# parallelmonitor.net
KiCad netlist of a schematic drawn in EAGLE
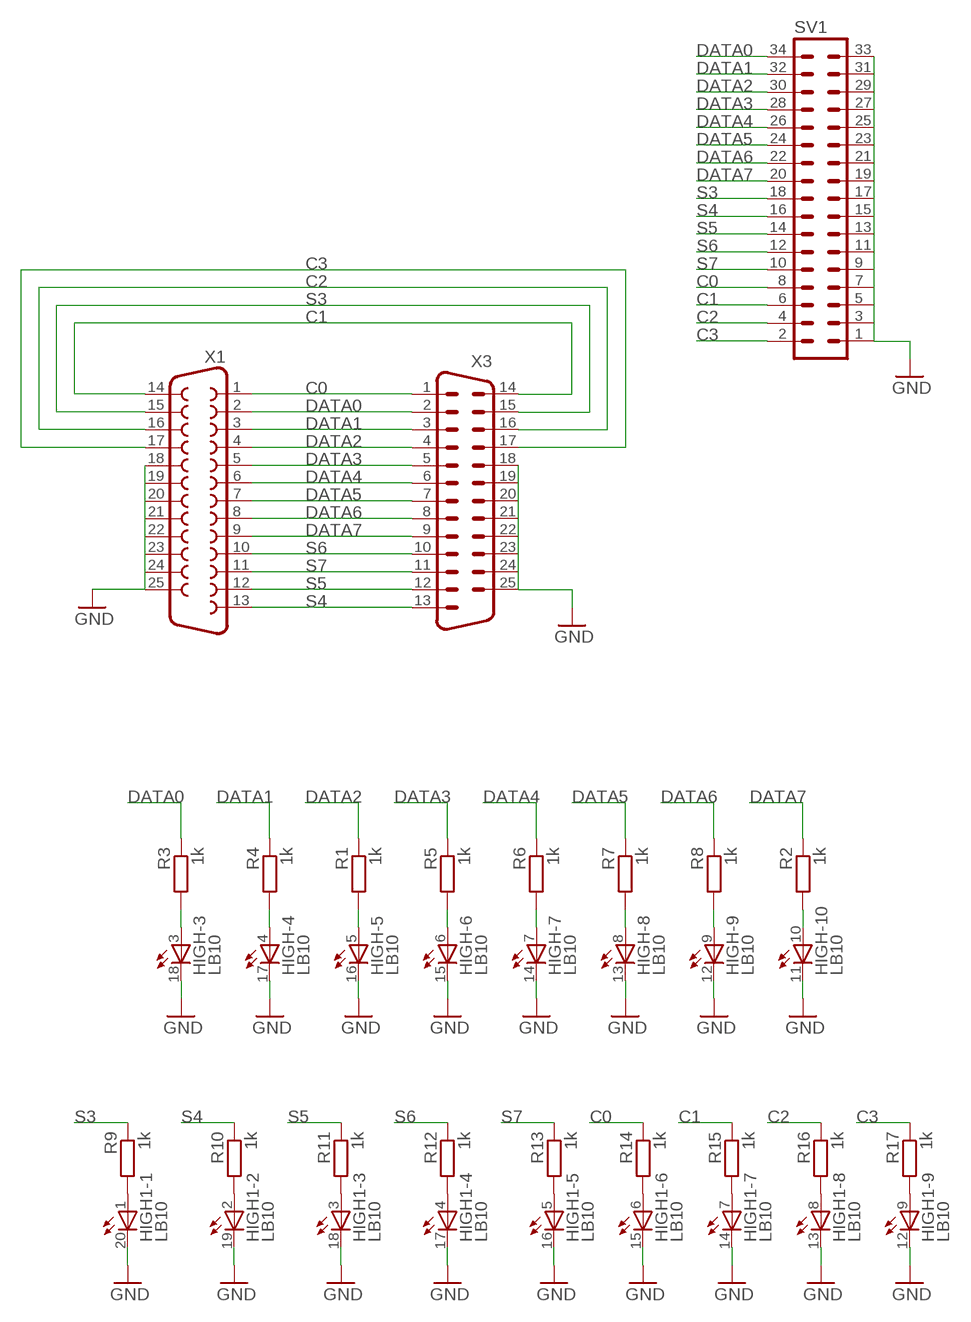
[diagram p0: schematic, sheet 1]

(export (version "E")
  (design (tool "Eeschema 10.0.6"))
  (components
    (comp (ref "HIGH")
      (value "LB10")
      (footprint "eagle-import:LB10")
      (libsource (lib "eagle-import") (part "LB10"))
    )
    (comp (ref "HIGH1")
      (value "LB10")
      (footprint "eagle-import:LB10")
      (libsource (lib "eagle-import") (part "LB10"))
    )
    (comp (ref "R1")
      (value "1k")
      (footprint "eagle-import:M0805")
      (libsource (lib "eagle-import") (part "R-EU_M0805"))
    )
    (comp (ref "R2")
      (value "1k")
      (footprint "eagle-import:M0805")
      (libsource (lib "eagle-import") (part "R-EU_M0805"))
    )
    (comp (ref "R3")
      (value "1k")
      (footprint "eagle-import:M0805")
      (libsource (lib "eagle-import") (part "R-EU_M0805"))
    )
    (comp (ref "R4")
      (value "1k")
      (footprint "eagle-import:M0805")
      (libsource (lib "eagle-import") (part "R-EU_M0805"))
    )
    (comp (ref "R5")
      (value "1k")
      (footprint "eagle-import:M0805")
      (libsource (lib "eagle-import") (part "R-EU_M0805"))
    )
    (comp (ref "R6")
      (value "1k")
      (footprint "eagle-import:M0805")
      (libsource (lib "eagle-import") (part "R-EU_M0805"))
    )
    (comp (ref "R7")
      (value "1k")
      (footprint "eagle-import:M0805")
      (libsource (lib "eagle-import") (part "R-EU_M0805"))
    )
    (comp (ref "R8")
      (value "1k")
      (footprint "eagle-import:M0805")
      (libsource (lib "eagle-import") (part "R-EU_M0805"))
    )
    (comp (ref "R9")
      (value "1k")
      (footprint "eagle-import:M0805")
      (libsource (lib "eagle-import") (part "R-EU_M0805"))
    )
    (comp (ref "R10")
      (value "1k")
      (footprint "eagle-import:M0805")
      (libsource (lib "eagle-import") (part "R-EU_M0805"))
    )
    (comp (ref "R11")
      (value "1k")
      (footprint "eagle-import:M0805")
      (libsource (lib "eagle-import") (part "R-EU_M0805"))
    )
    (comp (ref "R12")
      (value "1k")
      (footprint "eagle-import:M0805")
      (libsource (lib "eagle-import") (part "R-EU_M0805"))
    )
    (comp (ref "R13")
      (value "1k")
      (footprint "eagle-import:M0805")
      (libsource (lib "eagle-import") (part "R-EU_M0805"))
    )
    (comp (ref "R14")
      (value "1k")
      (footprint "eagle-import:M0805")
      (libsource (lib "eagle-import") (part "R-EU_M0805"))
    )
    (comp (ref "R15")
      (value "1k")
      (footprint "eagle-import:M0805")
      (libsource (lib "eagle-import") (part "R-EU_M0805"))
    )
    (comp (ref "R16")
      (value "1k")
      (footprint "eagle-import:M0805")
      (libsource (lib "eagle-import") (part "R-EU_M0805"))
    )
    (comp (ref "R17")
      (value "1k")
      (footprint "eagle-import:M0805")
      (libsource (lib "eagle-import") (part "R-EU_M0805"))
    )
    (comp (ref "SV1")
      (value "MA17-2W")
      (footprint "eagle-import:MA17-2W")
      (libsource (lib "eagle-import") (part "MA17-2W"))
    )
    (comp (ref "X1")
      (value "F25D")
      (footprint "eagle-import:F25D")
      (libsource (lib "eagle-import") (part "F25D"))
    )
    (comp (ref "X3")
      (value "M25D")
      (footprint "eagle-import:M25D")
      (libsource (lib "eagle-import") (part "M25D"))
    )
  )
  (nets
    (net (code "1") (name "/C0") (class "Default")
      (node (ref "R14") (pin "1") (pinfunction "1_1") (pintype "passive"))
      (node (ref "SV1") (pin "8") (pinfunction "8_8") (pintype "passive"))
      (node (ref "X1") (pin "1") (pinfunction "1_1") (pintype "passive"))
      (node (ref "X3") (pin "1") (pinfunction "1_1") (pintype "passive"))
    )
    (net (code "2") (name "/C1") (class "Default")
      (node (ref "R15") (pin "1") (pinfunction "1_1") (pintype "passive"))
      (node (ref "SV1") (pin "6") (pinfunction "6_6") (pintype "passive"))
      (node (ref "X1") (pin "14") (pinfunction "14_14") (pintype "passive"))
      (node (ref "X3") (pin "14") (pinfunction "14_14") (pintype "passive"))
    )
    (net (code "3") (name "/C2") (class "Default")
      (node (ref "R16") (pin "1") (pinfunction "1_1") (pintype "passive"))
      (node (ref "SV1") (pin "4") (pinfunction "4_4") (pintype "passive"))
      (node (ref "X1") (pin "16") (pinfunction "16_16") (pintype "passive"))
      (node (ref "X3") (pin "16") (pinfunction "16_16") (pintype "passive"))
    )
    (net (code "4") (name "/C3") (class "Default")
      (node (ref "R17") (pin "1") (pinfunction "1_1") (pintype "passive"))
      (node (ref "SV1") (pin "2") (pinfunction "2_2") (pintype "passive"))
      (node (ref "X1") (pin "17") (pinfunction "17_17") (pintype "passive"))
      (node (ref "X3") (pin "17") (pinfunction "17_17") (pintype "passive"))
    )
    (net (code "5") (name "/DATA0") (class "Default")
      (node (ref "R3") (pin "1") (pinfunction "1_1") (pintype "passive"))
      (node (ref "SV1") (pin "34") (pinfunction "34_34") (pintype "passive"))
      (node (ref "X1") (pin "2") (pinfunction "2_2") (pintype "passive"))
      (node (ref "X3") (pin "2") (pinfunction "2_2") (pintype "passive"))
    )
    (net (code "6") (name "/DATA1") (class "Default")
      (node (ref "R4") (pin "1") (pinfunction "1_1") (pintype "passive"))
      (node (ref "SV1") (pin "32") (pinfunction "32_32") (pintype "passive"))
      (node (ref "X1") (pin "3") (pinfunction "3_3") (pintype "passive"))
      (node (ref "X3") (pin "3") (pinfunction "3_3") (pintype "passive"))
    )
    (net (code "7") (name "/DATA2") (class "Default")
      (node (ref "R1") (pin "1") (pinfunction "1_1") (pintype "passive"))
      (node (ref "SV1") (pin "30") (pinfunction "30_30") (pintype "passive"))
      (node (ref "X1") (pin "4") (pinfunction "4_4") (pintype "passive"))
      (node (ref "X3") (pin "4") (pinfunction "4_4") (pintype "passive"))
    )
    (net (code "8") (name "/DATA3") (class "Default")
      (node (ref "R5") (pin "1") (pinfunction "1_1") (pintype "passive"))
      (node (ref "SV1") (pin "28") (pinfunction "28_28") (pintype "passive"))
      (node (ref "X1") (pin "5") (pinfunction "5_5") (pintype "passive"))
      (node (ref "X3") (pin "5") (pinfunction "5_5") (pintype "passive"))
    )
    (net (code "9") (name "/DATA4") (class "Default")
      (node (ref "R6") (pin "1") (pinfunction "1_1") (pintype "passive"))
      (node (ref "SV1") (pin "26") (pinfunction "26_26") (pintype "passive"))
      (node (ref "X1") (pin "6") (pinfunction "6_6") (pintype "passive"))
      (node (ref "X3") (pin "6") (pinfunction "6_6") (pintype "passive"))
    )
    (net (code "10") (name "/DATA5") (class "Default")
      (node (ref "R7") (pin "1") (pinfunction "1_1") (pintype "passive"))
      (node (ref "SV1") (pin "24") (pinfunction "24_24") (pintype "passive"))
      (node (ref "X1") (pin "7") (pinfunction "7_7") (pintype "passive"))
      (node (ref "X3") (pin "7") (pinfunction "7_7") (pintype "passive"))
    )
    (net (code "11") (name "/DATA6") (class "Default")
      (node (ref "R8") (pin "1") (pinfunction "1_1") (pintype "passive"))
      (node (ref "SV1") (pin "22") (pinfunction "22_22") (pintype "passive"))
      (node (ref "X1") (pin "8") (pinfunction "8_8") (pintype "passive"))
      (node (ref "X3") (pin "8") (pinfunction "8_8") (pintype "passive"))
    )
    (net (code "12") (name "/DATA7") (class "Default")
      (node (ref "R2") (pin "1") (pinfunction "1_1") (pintype "passive"))
      (node (ref "SV1") (pin "20") (pinfunction "20_20") (pintype "passive"))
      (node (ref "X1") (pin "9") (pinfunction "9_9") (pintype "passive"))
      (node (ref "X3") (pin "9") (pinfunction "9_9") (pintype "passive"))
    )
    (net (code "13") (name "/S3") (class "Default")
      (node (ref "R9") (pin "1") (pinfunction "1_1") (pintype "passive"))
      (node (ref "SV1") (pin "18") (pinfunction "18_18") (pintype "passive"))
      (node (ref "X1") (pin "15") (pinfunction "15_15") (pintype "passive"))
      (node (ref "X3") (pin "15") (pinfunction "15_15") (pintype "passive"))
    )
    (net (code "14") (name "/S4") (class "Default")
      (node (ref "R10") (pin "1") (pinfunction "1_1") (pintype "passive"))
      (node (ref "SV1") (pin "16") (pinfunction "16_16") (pintype "passive"))
      (node (ref "X1") (pin "13") (pinfunction "13_13") (pintype "passive"))
      (node (ref "X3") (pin "13") (pinfunction "13_13") (pintype "passive"))
    )
    (net (code "15") (name "/S5") (class "Default")
      (node (ref "R11") (pin "1") (pinfunction "1_1") (pintype "passive"))
      (node (ref "SV1") (pin "14") (pinfunction "14_14") (pintype "passive"))
      (node (ref "X1") (pin "12") (pinfunction "12_12") (pintype "passive"))
      (node (ref "X3") (pin "12") (pinfunction "12_12") (pintype "passive"))
    )
    (net (code "16") (name "/S6") (class "Default")
      (node (ref "R12") (pin "1") (pinfunction "1_1") (pintype "passive"))
      (node (ref "SV1") (pin "12") (pinfunction "12_12") (pintype "passive"))
      (node (ref "X1") (pin "10") (pinfunction "10_10") (pintype "passive"))
      (node (ref "X3") (pin "10") (pinfunction "10_10") (pintype "passive"))
    )
    (net (code "17") (name "/S7") (class "Default")
      (node (ref "R13") (pin "1") (pinfunction "1_1") (pintype "passive"))
      (node (ref "SV1") (pin "10") (pinfunction "10_10") (pintype "passive"))
      (node (ref "X1") (pin "11") (pinfunction "11_11") (pintype "passive"))
      (node (ref "X3") (pin "11") (pinfunction "11_11") (pintype "passive"))
    )
    (net (code "18") (name "GND") (class "Default")
      (node (ref "HIGH") (pin "11") (pinfunction "C_11") (pintype "passive"))
      (node (ref "HIGH") (pin "12") (pinfunction "C_12") (pintype "passive"))
      (node (ref "HIGH") (pin "13") (pinfunction "C_13") (pintype "passive"))
      (node (ref "HIGH") (pin "14") (pinfunction "C_14") (pintype "passive"))
      (node (ref "HIGH") (pin "15") (pinfunction "C_15") (pintype "passive"))
      (node (ref "HIGH") (pin "16") (pinfunction "C_16") (pintype "passive"))
      (node (ref "HIGH") (pin "17") (pinfunction "C_17") (pintype "passive"))
      (node (ref "HIGH") (pin "18") (pinfunction "C_18") (pintype "passive"))
      (node (ref "HIGH1") (pin "12") (pinfunction "C_12") (pintype "passive"))
      (node (ref "HIGH1") (pin "13") (pinfunction "C_13") (pintype "passive"))
      (node (ref "HIGH1") (pin "14") (pinfunction "C_14") (pintype "passive"))
      (node (ref "HIGH1") (pin "15") (pinfunction "C_15") (pintype "passive"))
      (node (ref "HIGH1") (pin "16") (pinfunction "C_16") (pintype "passive"))
      (node (ref "HIGH1") (pin "17") (pinfunction "C_17") (pintype "passive"))
      (node (ref "HIGH1") (pin "18") (pinfunction "C_18") (pintype "passive"))
      (node (ref "HIGH1") (pin "19") (pinfunction "C_19") (pintype "passive"))
      (node (ref "HIGH1") (pin "20") (pinfunction "C_20") (pintype "passive"))
      (node (ref "SV1") (pin "1") (pinfunction "1_1") (pintype "passive"))
      (node (ref "SV1") (pin "11") (pinfunction "11_11") (pintype "passive"))
      (node (ref "SV1") (pin "13") (pinfunction "13_13") (pintype "passive"))
      (node (ref "SV1") (pin "15") (pinfunction "15_15") (pintype "passive"))
      (node (ref "SV1") (pin "17") (pinfunction "17_17") (pintype "passive"))
      (node (ref "SV1") (pin "19") (pinfunction "19_19") (pintype "passive"))
      (node (ref "SV1") (pin "21") (pinfunction "21_21") (pintype "passive"))
      (node (ref "SV1") (pin "23") (pinfunction "23_23") (pintype "passive"))
      (node (ref "SV1") (pin "25") (pinfunction "25_25") (pintype "passive"))
      (node (ref "SV1") (pin "27") (pinfunction "27_27") (pintype "passive"))
      (node (ref "SV1") (pin "29") (pinfunction "29_29") (pintype "passive"))
      (node (ref "SV1") (pin "3") (pinfunction "3_3") (pintype "passive"))
      (node (ref "SV1") (pin "31") (pinfunction "31_31") (pintype "passive"))
      (node (ref "SV1") (pin "33") (pinfunction "33_33") (pintype "passive"))
      (node (ref "SV1") (pin "5") (pinfunction "5_5") (pintype "passive"))
      (node (ref "SV1") (pin "7") (pinfunction "7_7") (pintype "passive"))
      (node (ref "SV1") (pin "9") (pinfunction "9_9") (pintype "passive"))
      (node (ref "X1") (pin "18") (pinfunction "18_18") (pintype "passive"))
      (node (ref "X1") (pin "19") (pinfunction "19_19") (pintype "passive"))
      (node (ref "X1") (pin "20") (pinfunction "20_20") (pintype "passive"))
      (node (ref "X1") (pin "21") (pinfunction "21_21") (pintype "passive"))
      (node (ref "X1") (pin "22") (pinfunction "22_22") (pintype "passive"))
      (node (ref "X1") (pin "23") (pinfunction "23_23") (pintype "passive"))
      (node (ref "X1") (pin "24") (pinfunction "24_24") (pintype "passive"))
      (node (ref "X1") (pin "25") (pinfunction "25_25") (pintype "passive"))
      (node (ref "X3") (pin "18") (pinfunction "18_18") (pintype "passive"))
      (node (ref "X3") (pin "19") (pinfunction "19_19") (pintype "passive"))
      (node (ref "X3") (pin "20") (pinfunction "20_20") (pintype "passive"))
      (node (ref "X3") (pin "21") (pinfunction "21_21") (pintype "passive"))
      (node (ref "X3") (pin "22") (pinfunction "22_22") (pintype "passive"))
      (node (ref "X3") (pin "23") (pinfunction "23_23") (pintype "passive"))
      (node (ref "X3") (pin "24") (pinfunction "24_24") (pintype "passive"))
      (node (ref "X3") (pin "25") (pinfunction "25_25") (pintype "passive"))
    )
    (net (code "19") (name "Net-(HIGH1A-A)") (class "Default")
      (node (ref "HIGH1") (pin "1") (pinfunction "A_1") (pintype "passive"))
      (node (ref "R9") (pin "2") (pinfunction "2_2") (pintype "passive"))
    )
    (net (code "20") (name "Net-(HIGH1C-A)") (class "Default")
      (node (ref "HIGH1") (pin "2") (pinfunction "A_2") (pintype "passive"))
      (node (ref "R10") (pin "2") (pinfunction "2_2") (pintype "passive"))
    )
    (net (code "21") (name "Net-(HIGH1D-A)") (class "Default")
      (node (ref "HIGH1") (pin "3") (pinfunction "A_3") (pintype "passive"))
      (node (ref "R11") (pin "2") (pinfunction "2_2") (pintype "passive"))
    )
    (net (code "22") (name "Net-(HIGH1E-A)") (class "Default")
      (node (ref "HIGH1") (pin "4") (pinfunction "A_4") (pintype "passive"))
      (node (ref "R12") (pin "2") (pinfunction "2_2") (pintype "passive"))
    )
    (net (code "23") (name "Net-(HIGH1F-A)") (class "Default")
      (node (ref "HIGH1") (pin "5") (pinfunction "A_5") (pintype "passive"))
      (node (ref "R13") (pin "2") (pinfunction "2_2") (pintype "passive"))
    )
    (net (code "24") (name "Net-(HIGH1G-A)") (class "Default")
      (node (ref "HIGH1") (pin "6") (pinfunction "A_6") (pintype "passive"))
      (node (ref "R14") (pin "2") (pinfunction "2_2") (pintype "passive"))
    )
    (net (code "25") (name "Net-(HIGH1H-A)") (class "Default")
      (node (ref "HIGH1") (pin "7") (pinfunction "A_7") (pintype "passive"))
      (node (ref "R15") (pin "2") (pinfunction "2_2") (pintype "passive"))
    )
    (net (code "26") (name "Net-(HIGH1I-A)") (class "Default")
      (node (ref "HIGH1") (pin "8") (pinfunction "A_8") (pintype "passive"))
      (node (ref "R16") (pin "2") (pinfunction "2_2") (pintype "passive"))
    )
    (net (code "27") (name "Net-(HIGH1J-A)") (class "Default")
      (node (ref "HIGH1") (pin "9") (pinfunction "A_9") (pintype "passive"))
      (node (ref "R17") (pin "2") (pinfunction "2_2") (pintype "passive"))
    )
    (net (code "28") (name "Net-(HIGHB-A)") (class "Default")
      (node (ref "HIGH") (pin "10") (pinfunction "A_10") (pintype "passive"))
      (node (ref "R2") (pin "2") (pinfunction "2_2") (pintype "passive"))
    )
    (net (code "29") (name "Net-(HIGHD-A)") (class "Default")
      (node (ref "HIGH") (pin "3") (pinfunction "A_3") (pintype "passive"))
      (node (ref "R3") (pin "2") (pinfunction "2_2") (pintype "passive"))
    )
    (net (code "30") (name "Net-(HIGHE-A)") (class "Default")
      (node (ref "HIGH") (pin "4") (pinfunction "A_4") (pintype "passive"))
      (node (ref "R4") (pin "2") (pinfunction "2_2") (pintype "passive"))
    )
    (net (code "31") (name "Net-(HIGHF-A)") (class "Default")
      (node (ref "HIGH") (pin "5") (pinfunction "A_5") (pintype "passive"))
      (node (ref "R1") (pin "2") (pinfunction "2_2") (pintype "passive"))
    )
    (net (code "32") (name "Net-(HIGHG-A)") (class "Default")
      (node (ref "HIGH") (pin "6") (pinfunction "A_6") (pintype "passive"))
      (node (ref "R5") (pin "2") (pinfunction "2_2") (pintype "passive"))
    )
    (net (code "33") (name "Net-(HIGHH-A)") (class "Default")
      (node (ref "HIGH") (pin "7") (pinfunction "A_7") (pintype "passive"))
      (node (ref "R6") (pin "2") (pinfunction "2_2") (pintype "passive"))
    )
    (net (code "34") (name "Net-(HIGHI-A)") (class "Default")
      (node (ref "HIGH") (pin "8") (pinfunction "A_8") (pintype "passive"))
      (node (ref "R7") (pin "2") (pinfunction "2_2") (pintype "passive"))
    )
    (net (code "35") (name "Net-(HIGHJ-A)") (class "Default")
      (node (ref "HIGH") (pin "9") (pinfunction "A_9") (pintype "passive"))
      (node (ref "R8") (pin "2") (pinfunction "2_2") (pintype "passive"))
    )
  )
)
